# eGAN-FET-module_Logic.net
KiCad netlist of a schematic drawn in Altium Designer
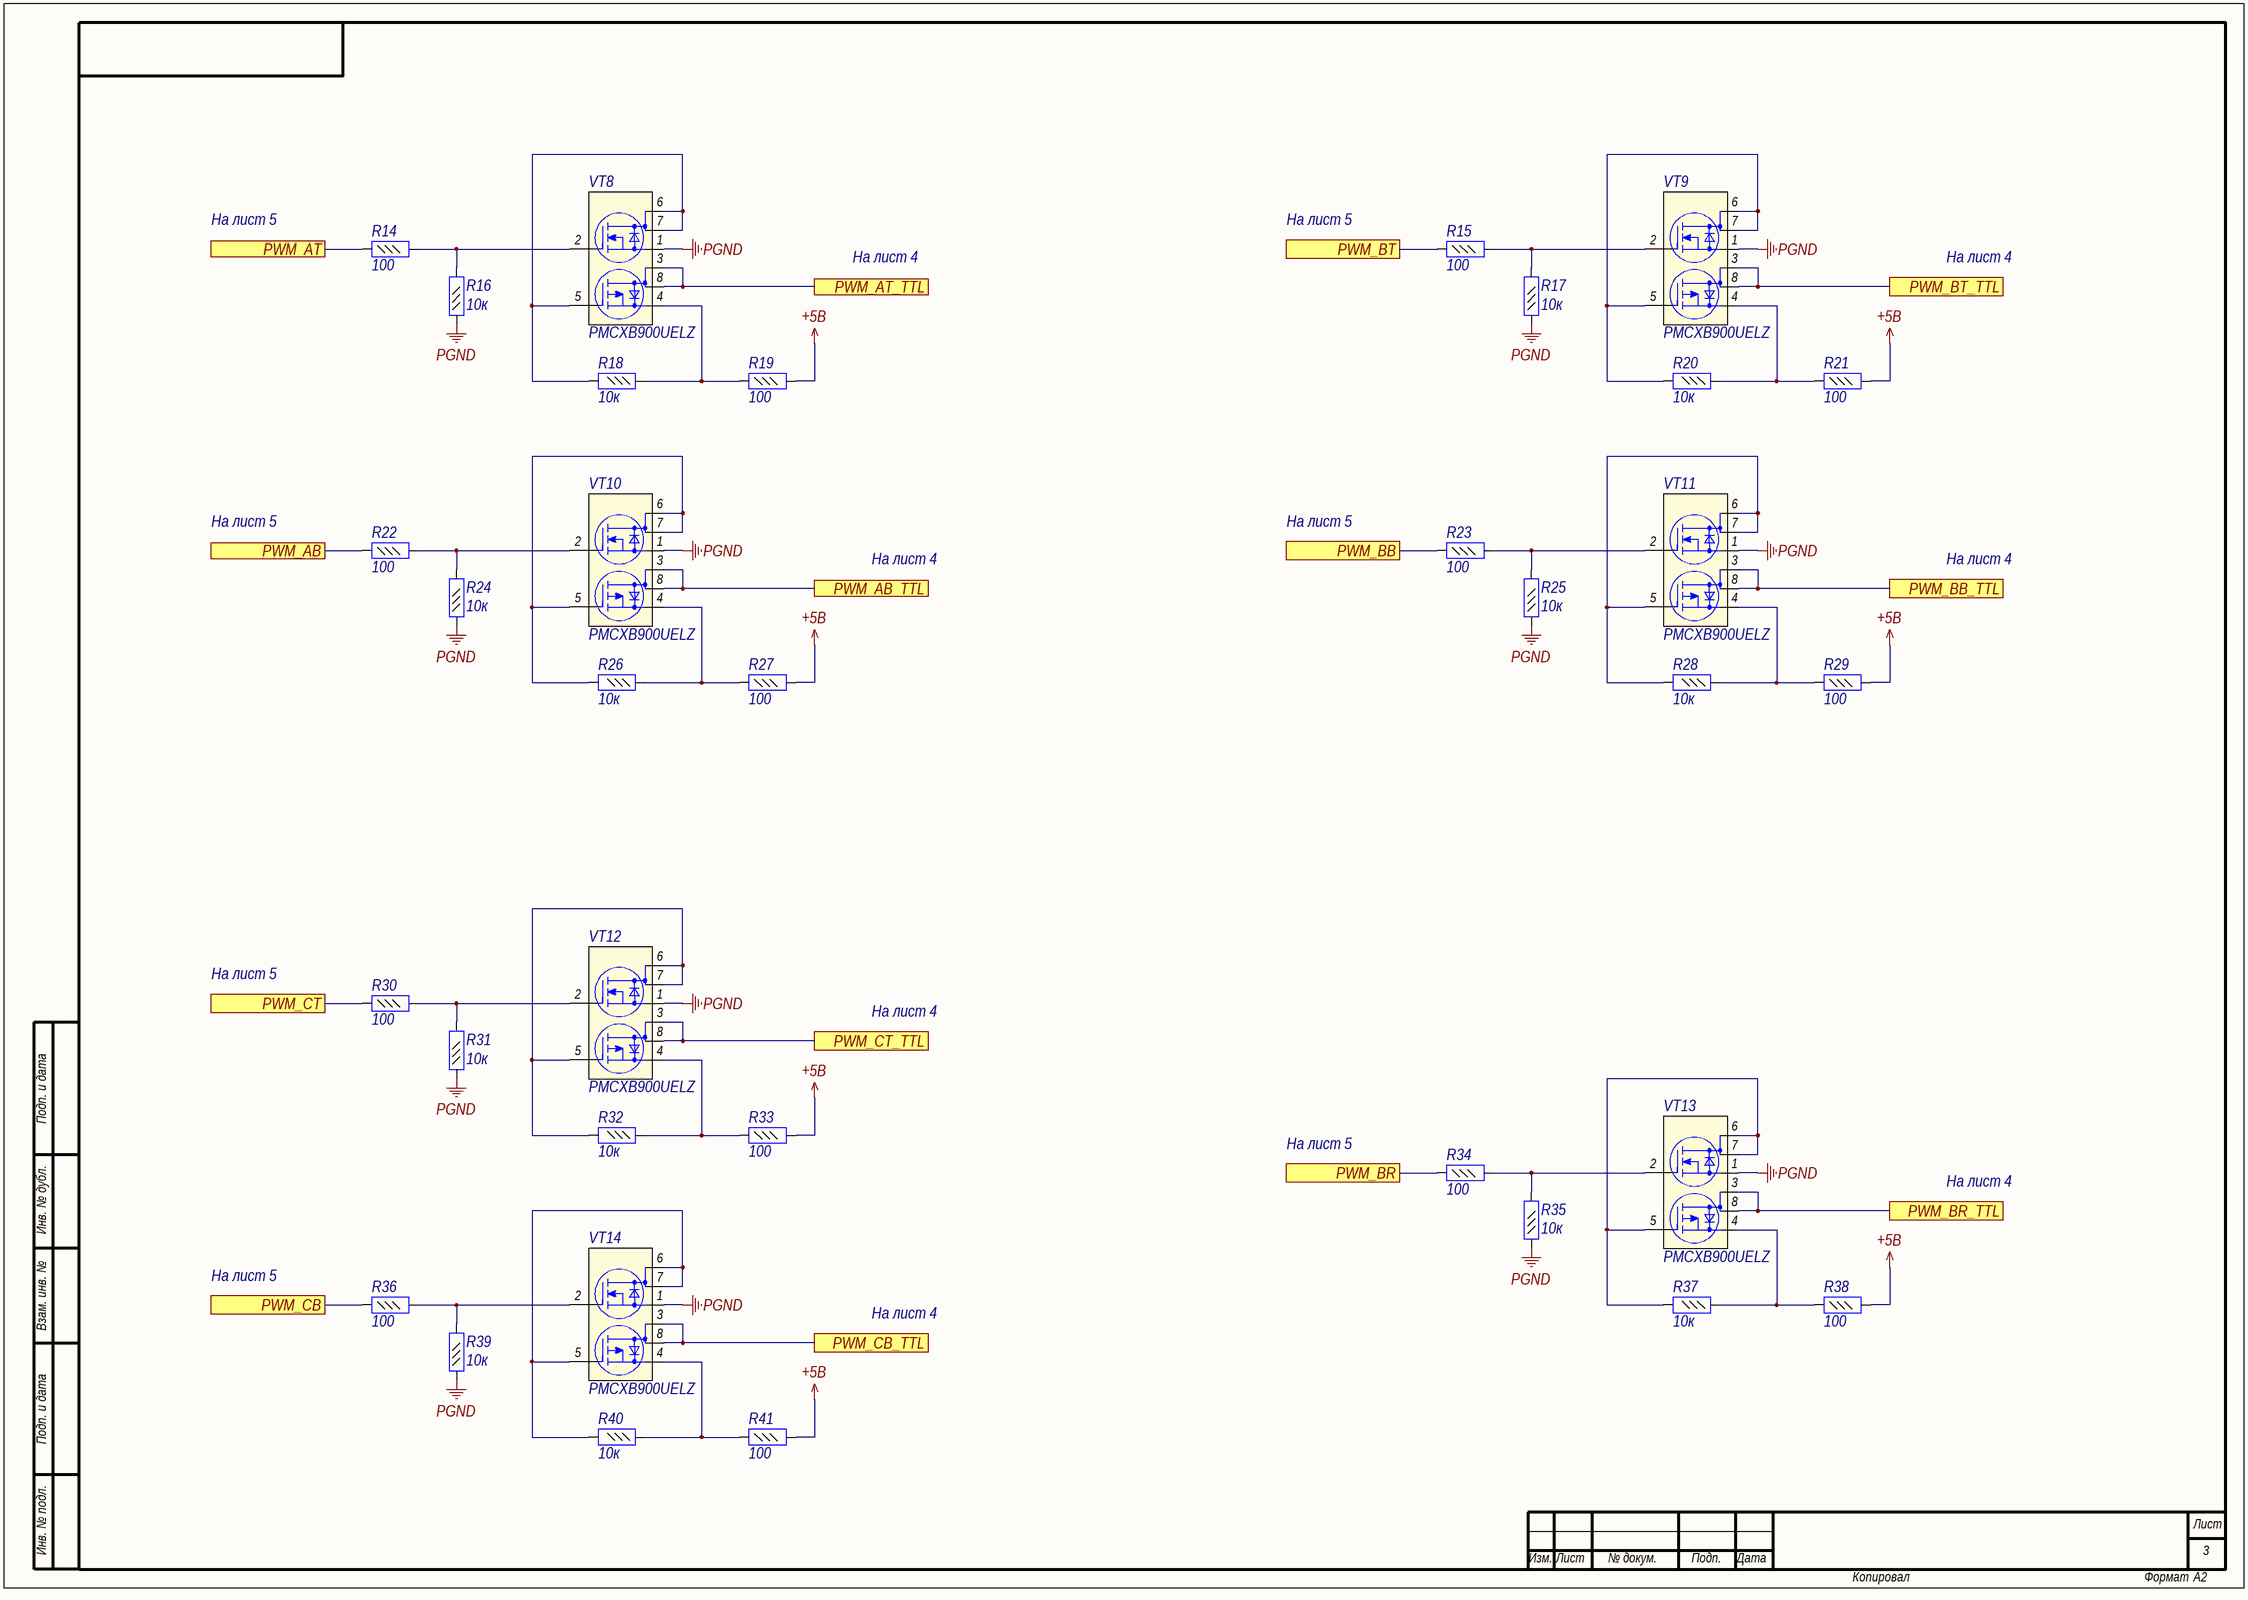
[diagram p0: eGAN-FET-module_Logic.SchDoc]

(export (version "E")
  (design (tool "Eeschema 10.0.6"))
  (components
    (comp (ref "R14")
      (value "100")
      (footprint "R0402")
      (description "Резистор")
      (fields (field (name "PART NUMBER") "RC0402FR-07100RL") (field (name "POWER") "0,062Вт"))
      (libsource (lib "") (part "Resistor_0,062Вт_2"))
    )
    (comp (ref "R15")
      (value "100")
      (footprint "R0402")
      (description "Резистор")
      (fields (field (name "PART NUMBER") "RC0402FR-07100RL") (field (name "POWER") "0,062Вт"))
      (libsource (lib "") (part "Resistor_0,062Вт_2"))
    )
    (comp (ref "R16")
      (value "10к")
      (footprint "R0402")
      (description "Резистор")
      (fields (field (name "PART NUMBER") "RC0402FR-0710KL") (field (name "POWER") "0,062Вт"))
      (libsource (lib "MOP44") (part "Resistor_0,062Вт"))
    )
    (comp (ref "R17")
      (value "10к")
      (footprint "R0402")
      (description "Резистор")
      (fields (field (name "PART NUMBER") "RC0402FR-0710KL") (field (name "POWER") "0,062Вт"))
      (libsource (lib "MOP44") (part "Resistor_0,062Вт"))
    )
    (comp (ref "R18")
      (value "10к")
      (footprint "R0402")
      (description "Резистор")
      (fields (field (name "PART NUMBER") "RC0402FR-0710KL") (field (name "POWER") "0,062Вт"))
      (libsource (lib "") (part "Resistor_0,062Вт_1"))
    )
    (comp (ref "R19")
      (value "100")
      (footprint "R0402")
      (description "Резистор")
      (fields (field (name "PART NUMBER") "RC0402FR-07100RL") (field (name "POWER") "0,062Вт"))
      (libsource (lib "") (part "Resistor_0,062Вт_2"))
    )
    (comp (ref "R20")
      (value "10к")
      (footprint "R0402")
      (description "Резистор")
      (fields (field (name "PART NUMBER") "RC0402FR-0710KL") (field (name "POWER") "0,062Вт"))
      (libsource (lib "") (part "Resistor_0,062Вт_1"))
    )
    (comp (ref "R21")
      (value "100")
      (footprint "R0402")
      (description "Резистор")
      (fields (field (name "PART NUMBER") "RC0402FR-07100RL") (field (name "POWER") "0,062Вт"))
      (libsource (lib "") (part "Resistor_0,062Вт_2"))
    )
    (comp (ref "R22")
      (value "100")
      (footprint "R0402")
      (description "Резистор")
      (fields (field (name "PART NUMBER") "RC0402FR-07100RL") (field (name "POWER") "0,062Вт"))
      (libsource (lib "") (part "Resistor_0,062Вт_2"))
    )
    (comp (ref "R23")
      (value "100")
      (footprint "R0402")
      (description "Резистор")
      (fields (field (name "PART NUMBER") "RC0402FR-07100RL") (field (name "POWER") "0,062Вт"))
      (libsource (lib "") (part "Resistor_0,062Вт_2"))
    )
    (comp (ref "R24")
      (value "10к")
      (footprint "R0402")
      (description "Резистор")
      (fields (field (name "PART NUMBER") "RC0402FR-0710KL") (field (name "POWER") "0,062Вт"))
      (libsource (lib "MOP44") (part "Resistor_0,062Вт"))
    )
    (comp (ref "R25")
      (value "10к")
      (footprint "R0402")
      (description "Резистор")
      (fields (field (name "PART NUMBER") "RC0402FR-0710KL") (field (name "POWER") "0,062Вт"))
      (libsource (lib "MOP44") (part "Resistor_0,062Вт"))
    )
    (comp (ref "R26")
      (value "10к")
      (footprint "R0402")
      (description "Резистор")
      (fields (field (name "PART NUMBER") "RC0402FR-0710KL") (field (name "POWER") "0,062Вт"))
      (libsource (lib "") (part "Resistor_0,062Вт_1"))
    )
    (comp (ref "R27")
      (value "100")
      (footprint "R0402")
      (description "Резистор")
      (fields (field (name "PART NUMBER") "RC0402FR-07100RL") (field (name "POWER") "0,062Вт"))
      (libsource (lib "") (part "Resistor_0,062Вт_2"))
    )
    (comp (ref "R28")
      (value "10к")
      (footprint "R0402")
      (description "Резистор")
      (fields (field (name "PART NUMBER") "RC0402FR-0710KL") (field (name "POWER") "0,062Вт"))
      (libsource (lib "") (part "Resistor_0,062Вт_1"))
    )
    (comp (ref "R29")
      (value "100")
      (footprint "R0402")
      (description "Резистор")
      (fields (field (name "PART NUMBER") "RC0402FR-07100RL") (field (name "POWER") "0,062Вт"))
      (libsource (lib "") (part "Resistor_0,062Вт_2"))
    )
    (comp (ref "R30")
      (value "100")
      (footprint "R0402")
      (description "Резистор")
      (fields (field (name "PART NUMBER") "RC0402FR-07100RL") (field (name "POWER") "0,062Вт"))
      (libsource (lib "") (part "Resistor_0,062Вт_2"))
    )
    (comp (ref "R31")
      (value "10к")
      (footprint "R0402")
      (description "Резистор")
      (fields (field (name "PART NUMBER") "RC0402FR-0710KL") (field (name "POWER") "0,062Вт"))
      (libsource (lib "MOP44") (part "Resistor_0,062Вт"))
    )
    (comp (ref "R32")
      (value "10к")
      (footprint "R0402")
      (description "Резистор")
      (fields (field (name "PART NUMBER") "RC0402FR-0710KL") (field (name "POWER") "0,062Вт"))
      (libsource (lib "") (part "Resistor_0,062Вт_1"))
    )
    (comp (ref "R33")
      (value "100")
      (footprint "R0402")
      (description "Резистор")
      (fields (field (name "PART NUMBER") "RC0402FR-07100RL") (field (name "POWER") "0,062Вт"))
      (libsource (lib "") (part "Resistor_0,062Вт_2"))
    )
    (comp (ref "R34")
      (value "100")
      (footprint "R0402")
      (description "Резистор")
      (fields (field (name "PART NUMBER") "RC0402FR-07100RL") (field (name "POWER") "0,062Вт"))
      (libsource (lib "") (part "Resistor_0,062Вт_2"))
    )
    (comp (ref "R35")
      (value "10к")
      (footprint "R0402")
      (description "Резистор")
      (fields (field (name "PART NUMBER") "RC0402FR-0710KL") (field (name "POWER") "0,062Вт"))
      (libsource (lib "MOP44") (part "Resistor_0,062Вт"))
    )
    (comp (ref "R36")
      (value "100")
      (footprint "R0402")
      (description "Резистор")
      (fields (field (name "PART NUMBER") "RC0402FR-07100RL") (field (name "POWER") "0,062Вт"))
      (libsource (lib "") (part "Resistor_0,062Вт_2"))
    )
    (comp (ref "R37")
      (value "10к")
      (footprint "R0402")
      (description "Резистор")
      (fields (field (name "PART NUMBER") "RC0402FR-0710KL") (field (name "POWER") "0,062Вт"))
      (libsource (lib "") (part "Resistor_0,062Вт_1"))
    )
    (comp (ref "R38")
      (value "100")
      (footprint "R0402")
      (description "Резистор")
      (fields (field (name "PART NUMBER") "RC0402FR-07100RL") (field (name "POWER") "0,062Вт"))
      (libsource (lib "") (part "Resistor_0,062Вт_2"))
    )
    (comp (ref "R39")
      (value "10к")
      (footprint "R0402")
      (description "Резистор")
      (fields (field (name "PART NUMBER") "RC0402FR-0710KL") (field (name "POWER") "0,062Вт"))
      (libsource (lib "MOP44") (part "Resistor_0,062Вт"))
    )
    (comp (ref "R40")
      (value "10к")
      (footprint "R0402")
      (description "Резистор")
      (fields (field (name "PART NUMBER") "RC0402FR-0710KL") (field (name "POWER") "0,062Вт"))
      (libsource (lib "") (part "Resistor_0,062Вт_1"))
    )
    (comp (ref "R41")
      (value "100")
      (footprint "R0402")
      (description "Резистор")
      (fields (field (name "PART NUMBER") "RC0402FR-07100RL") (field (name "POWER") "0,062Вт"))
      (libsource (lib "") (part "Resistor_0,062Вт_2"))
    )
    (comp (ref "VT8")
      (value "PMCXB900UELZ")
      (footprint "SOT1216")
      (fields (field (name "MANUFACTURER") "Nexperia"))
      (libsource (lib "MOP44") (part "PMCXB900UEL"))
    )
    (comp (ref "VT9")
      (value "PMCXB900UELZ")
      (footprint "SOT1216")
      (fields (field (name "MANUFACTURER") "Nexperia"))
      (libsource (lib "MOP44") (part "PMCXB900UEL"))
    )
    (comp (ref "VT10")
      (value "PMCXB900UELZ")
      (footprint "SOT1216")
      (fields (field (name "MANUFACTURER") "Nexperia"))
      (libsource (lib "MOP44") (part "PMCXB900UEL"))
    )
    (comp (ref "VT11")
      (value "PMCXB900UELZ")
      (footprint "SOT1216")
      (fields (field (name "MANUFACTURER") "Nexperia"))
      (libsource (lib "MOP44") (part "PMCXB900UEL"))
    )
    (comp (ref "VT12")
      (value "PMCXB900UELZ")
      (footprint "SOT1216")
      (fields (field (name "MANUFACTURER") "Nexperia"))
      (libsource (lib "MOP44") (part "PMCXB900UEL"))
    )
    (comp (ref "VT13")
      (value "PMCXB900UELZ")
      (footprint "SOT1216")
      (fields (field (name "MANUFACTURER") "Nexperia"))
      (libsource (lib "MOP44") (part "PMCXB900UEL"))
    )
    (comp (ref "VT14")
      (value "PMCXB900UELZ")
      (footprint "SOT1216")
      (fields (field (name "MANUFACTURER") "Nexperia"))
      (libsource (lib "MOP44") (part "PMCXB900UEL"))
    )
  )
  (nets
    (net (code "1") (name "+5B") (class "Default")
      (node (ref "R19") (pin "2") (pinfunction "2_2") (pintype "passive"))
      (node (ref "R21") (pin "2") (pinfunction "2_2") (pintype "passive"))
      (node (ref "R27") (pin "2") (pinfunction "2_2") (pintype "passive"))
      (node (ref "R29") (pin "2") (pinfunction "2_2") (pintype "passive"))
      (node (ref "R33") (pin "2") (pinfunction "2_2") (pintype "passive"))
      (node (ref "R38") (pin "2") (pinfunction "2_2") (pintype "passive"))
      (node (ref "R41") (pin "2") (pinfunction "2_2") (pintype "passive"))
    )
    (net (code "2") (name "/PWM_AB") (class "Default")
      (node (ref "R22") (pin "1") (pinfunction "1_1") (pintype "passive"))
    )
    (net (code "3") (name "/PWM_AB_TTL") (class "Default")
      (node (ref "VT10") (pin "3") (pinfunction "D2_3") (pintype "passive"))
      (node (ref "VT10") (pin "8") (pinfunction "D2_8") (pintype "passive"))
    )
    (net (code "4") (name "/PWM_AT") (class "Default")
      (node (ref "R14") (pin "1") (pinfunction "1_1") (pintype "passive"))
    )
    (net (code "5") (name "/PWM_AT_TTL") (class "Default")
      (node (ref "VT8") (pin "3") (pinfunction "D2_3") (pintype "passive"))
      (node (ref "VT8") (pin "8") (pinfunction "D2_8") (pintype "passive"))
    )
    (net (code "6") (name "/PWM_BB") (class "Default")
      (node (ref "R23") (pin "1") (pinfunction "1_1") (pintype "passive"))
    )
    (net (code "7") (name "/PWM_BB_TTL") (class "Default")
      (node (ref "VT11") (pin "3") (pinfunction "D2_3") (pintype "passive"))
      (node (ref "VT11") (pin "8") (pinfunction "D2_8") (pintype "passive"))
    )
    (net (code "8") (name "/PWM_BR") (class "Default")
      (node (ref "R34") (pin "1") (pinfunction "1_1") (pintype "passive"))
    )
    (net (code "9") (name "/PWM_BR_TTL") (class "Default")
      (node (ref "VT13") (pin "3") (pinfunction "D2_3") (pintype "passive"))
      (node (ref "VT13") (pin "8") (pinfunction "D2_8") (pintype "passive"))
    )
    (net (code "10") (name "/PWM_BT") (class "Default")
      (node (ref "R15") (pin "1") (pinfunction "1_1") (pintype "passive"))
    )
    (net (code "11") (name "/PWM_BT_TTL") (class "Default")
      (node (ref "VT9") (pin "3") (pinfunction "D2_3") (pintype "passive"))
      (node (ref "VT9") (pin "8") (pinfunction "D2_8") (pintype "passive"))
    )
    (net (code "12") (name "/PWM_CB") (class "Default")
      (node (ref "R36") (pin "1") (pinfunction "1_1") (pintype "passive"))
    )
    (net (code "13") (name "/PWM_CB_TTL") (class "Default")
      (node (ref "VT14") (pin "3") (pinfunction "D2_3") (pintype "passive"))
      (node (ref "VT14") (pin "8") (pinfunction "D2_8") (pintype "passive"))
    )
    (net (code "14") (name "/PWM_CT") (class "Default")
      (node (ref "R30") (pin "1") (pinfunction "1_1") (pintype "passive"))
    )
    (net (code "15") (name "/PWM_CT_TTL") (class "Default")
      (node (ref "VT12") (pin "3") (pinfunction "D2_3") (pintype "passive"))
      (node (ref "VT12") (pin "8") (pinfunction "D2_8") (pintype "passive"))
    )
    (net (code "16") (name "Net-(VT8-G1)") (class "Default")
      (node (ref "R14") (pin "2") (pinfunction "2_2") (pintype "passive"))
      (node (ref "R16") (pin "2") (pinfunction "2_2") (pintype "passive"))
      (node (ref "VT8") (pin "2") (pinfunction "G1_2") (pintype "passive"))
    )
    (net (code "17") (name "Net-(VT8-G2)") (class "Default")
      (node (ref "R18") (pin "2") (pinfunction "2_2") (pintype "passive"))
      (node (ref "VT8") (pin "5") (pinfunction "G2_5") (pintype "passive"))
      (node (ref "VT8") (pin "6") (pinfunction "D1_6") (pintype "passive"))
      (node (ref "VT8") (pin "7") (pinfunction "D1_7") (pintype "passive"))
    )
    (net (code "18") (name "Net-(VT8-S2)") (class "Default")
      (node (ref "R18") (pin "1") (pinfunction "1_1") (pintype "passive"))
      (node (ref "R19") (pin "1") (pinfunction "1_1") (pintype "passive"))
      (node (ref "VT8") (pin "4") (pinfunction "S2_4") (pintype "passive"))
    )
    (net (code "19") (name "Net-(VT9-G1)") (class "Default")
      (node (ref "R15") (pin "2") (pinfunction "2_2") (pintype "passive"))
      (node (ref "R17") (pin "2") (pinfunction "2_2") (pintype "passive"))
      (node (ref "VT9") (pin "2") (pinfunction "G1_2") (pintype "passive"))
    )
    (net (code "20") (name "Net-(VT9-G2)") (class "Default")
      (node (ref "R20") (pin "2") (pinfunction "2_2") (pintype "passive"))
      (node (ref "VT9") (pin "5") (pinfunction "G2_5") (pintype "passive"))
      (node (ref "VT9") (pin "6") (pinfunction "D1_6") (pintype "passive"))
      (node (ref "VT9") (pin "7") (pinfunction "D1_7") (pintype "passive"))
    )
    (net (code "21") (name "Net-(VT9-S2)") (class "Default")
      (node (ref "R20") (pin "1") (pinfunction "1_1") (pintype "passive"))
      (node (ref "R21") (pin "1") (pinfunction "1_1") (pintype "passive"))
      (node (ref "VT9") (pin "4") (pinfunction "S2_4") (pintype "passive"))
    )
    (net (code "22") (name "Net-(VT10-G1)") (class "Default")
      (node (ref "R22") (pin "2") (pinfunction "2_2") (pintype "passive"))
      (node (ref "R24") (pin "2") (pinfunction "2_2") (pintype "passive"))
      (node (ref "VT10") (pin "2") (pinfunction "G1_2") (pintype "passive"))
    )
    (net (code "23") (name "Net-(VT10-G2)") (class "Default")
      (node (ref "R26") (pin "2") (pinfunction "2_2") (pintype "passive"))
      (node (ref "VT10") (pin "5") (pinfunction "G2_5") (pintype "passive"))
      (node (ref "VT10") (pin "6") (pinfunction "D1_6") (pintype "passive"))
      (node (ref "VT10") (pin "7") (pinfunction "D1_7") (pintype "passive"))
    )
    (net (code "24") (name "Net-(VT10-S2)") (class "Default")
      (node (ref "R26") (pin "1") (pinfunction "1_1") (pintype "passive"))
      (node (ref "R27") (pin "1") (pinfunction "1_1") (pintype "passive"))
      (node (ref "VT10") (pin "4") (pinfunction "S2_4") (pintype "passive"))
    )
    (net (code "25") (name "Net-(VT11-G1)") (class "Default")
      (node (ref "R23") (pin "2") (pinfunction "2_2") (pintype "passive"))
      (node (ref "R25") (pin "2") (pinfunction "2_2") (pintype "passive"))
      (node (ref "VT11") (pin "2") (pinfunction "G1_2") (pintype "passive"))
    )
    (net (code "26") (name "Net-(VT11-G2)") (class "Default")
      (node (ref "R28") (pin "2") (pinfunction "2_2") (pintype "passive"))
      (node (ref "VT11") (pin "5") (pinfunction "G2_5") (pintype "passive"))
      (node (ref "VT11") (pin "6") (pinfunction "D1_6") (pintype "passive"))
      (node (ref "VT11") (pin "7") (pinfunction "D1_7") (pintype "passive"))
    )
    (net (code "27") (name "Net-(VT11-S2)") (class "Default")
      (node (ref "R28") (pin "1") (pinfunction "1_1") (pintype "passive"))
      (node (ref "R29") (pin "1") (pinfunction "1_1") (pintype "passive"))
      (node (ref "VT11") (pin "4") (pinfunction "S2_4") (pintype "passive"))
    )
    (net (code "28") (name "Net-(VT12-G1)") (class "Default")
      (node (ref "R30") (pin "2") (pinfunction "2_2") (pintype "passive"))
      (node (ref "R31") (pin "2") (pinfunction "2_2") (pintype "passive"))
      (node (ref "VT12") (pin "2") (pinfunction "G1_2") (pintype "passive"))
    )
    (net (code "29") (name "Net-(VT12-G2)") (class "Default")
      (node (ref "R32") (pin "2") (pinfunction "2_2") (pintype "passive"))
      (node (ref "VT12") (pin "5") (pinfunction "G2_5") (pintype "passive"))
      (node (ref "VT12") (pin "6") (pinfunction "D1_6") (pintype "passive"))
      (node (ref "VT12") (pin "7") (pinfunction "D1_7") (pintype "passive"))
    )
    (net (code "30") (name "Net-(VT12-S2)") (class "Default")
      (node (ref "R32") (pin "1") (pinfunction "1_1") (pintype "passive"))
      (node (ref "R33") (pin "1") (pinfunction "1_1") (pintype "passive"))
      (node (ref "VT12") (pin "4") (pinfunction "S2_4") (pintype "passive"))
    )
    (net (code "31") (name "Net-(VT13-G1)") (class "Default")
      (node (ref "R34") (pin "2") (pinfunction "2_2") (pintype "passive"))
      (node (ref "R35") (pin "2") (pinfunction "2_2") (pintype "passive"))
      (node (ref "VT13") (pin "2") (pinfunction "G1_2") (pintype "passive"))
    )
    (net (code "32") (name "Net-(VT13-G2)") (class "Default")
      (node (ref "R37") (pin "2") (pinfunction "2_2") (pintype "passive"))
      (node (ref "VT13") (pin "5") (pinfunction "G2_5") (pintype "passive"))
      (node (ref "VT13") (pin "6") (pinfunction "D1_6") (pintype "passive"))
      (node (ref "VT13") (pin "7") (pinfunction "D1_7") (pintype "passive"))
    )
    (net (code "33") (name "Net-(VT13-S2)") (class "Default")
      (node (ref "R37") (pin "1") (pinfunction "1_1") (pintype "passive"))
      (node (ref "R38") (pin "1") (pinfunction "1_1") (pintype "passive"))
      (node (ref "VT13") (pin "4") (pinfunction "S2_4") (pintype "passive"))
    )
    (net (code "34") (name "Net-(VT14-G1)") (class "Default")
      (node (ref "R36") (pin "2") (pinfunction "2_2") (pintype "passive"))
      (node (ref "R39") (pin "2") (pinfunction "2_2") (pintype "passive"))
      (node (ref "VT14") (pin "2") (pinfunction "G1_2") (pintype "passive"))
    )
    (net (code "35") (name "Net-(VT14-G2)") (class "Default")
      (node (ref "R40") (pin "2") (pinfunction "2_2") (pintype "passive"))
      (node (ref "VT14") (pin "5") (pinfunction "G2_5") (pintype "passive"))
      (node (ref "VT14") (pin "6") (pinfunction "D1_6") (pintype "passive"))
      (node (ref "VT14") (pin "7") (pinfunction "D1_7") (pintype "passive"))
    )
    (net (code "36") (name "Net-(VT14-S2)") (class "Default")
      (node (ref "R40") (pin "1") (pinfunction "1_1") (pintype "passive"))
      (node (ref "R41") (pin "1") (pinfunction "1_1") (pintype "passive"))
      (node (ref "VT14") (pin "4") (pinfunction "S2_4") (pintype "passive"))
    )
    (net (code "37") (name "PGND") (class "Default")
      (node (ref "R16") (pin "1") (pinfunction "1_1") (pintype "passive"))
      (node (ref "R17") (pin "1") (pinfunction "1_1") (pintype "passive"))
      (node (ref "R24") (pin "1") (pinfunction "1_1") (pintype "passive"))
      (node (ref "R25") (pin "1") (pinfunction "1_1") (pintype "passive"))
      (node (ref "R31") (pin "1") (pinfunction "1_1") (pintype "passive"))
      (node (ref "R35") (pin "1") (pinfunction "1_1") (pintype "passive"))
      (node (ref "R39") (pin "1") (pinfunction "1_1") (pintype "passive"))
      (node (ref "VT10") (pin "1") (pinfunction "S1_1") (pintype "passive"))
      (node (ref "VT11") (pin "1") (pinfunction "S1_1") (pintype "passive"))
      (node (ref "VT12") (pin "1") (pinfunction "S1_1") (pintype "passive"))
      (node (ref "VT13") (pin "1") (pinfunction "S1_1") (pintype "passive"))
      (node (ref "VT14") (pin "1") (pinfunction "S1_1") (pintype "passive"))
      (node (ref "VT8") (pin "1") (pinfunction "S1_1") (pintype "passive"))
      (node (ref "VT9") (pin "1") (pinfunction "S1_1") (pintype "passive"))
    )
  )
)
